# Sensor8A_V2.net
KiCad netlist of a schematic drawn in EAGLE
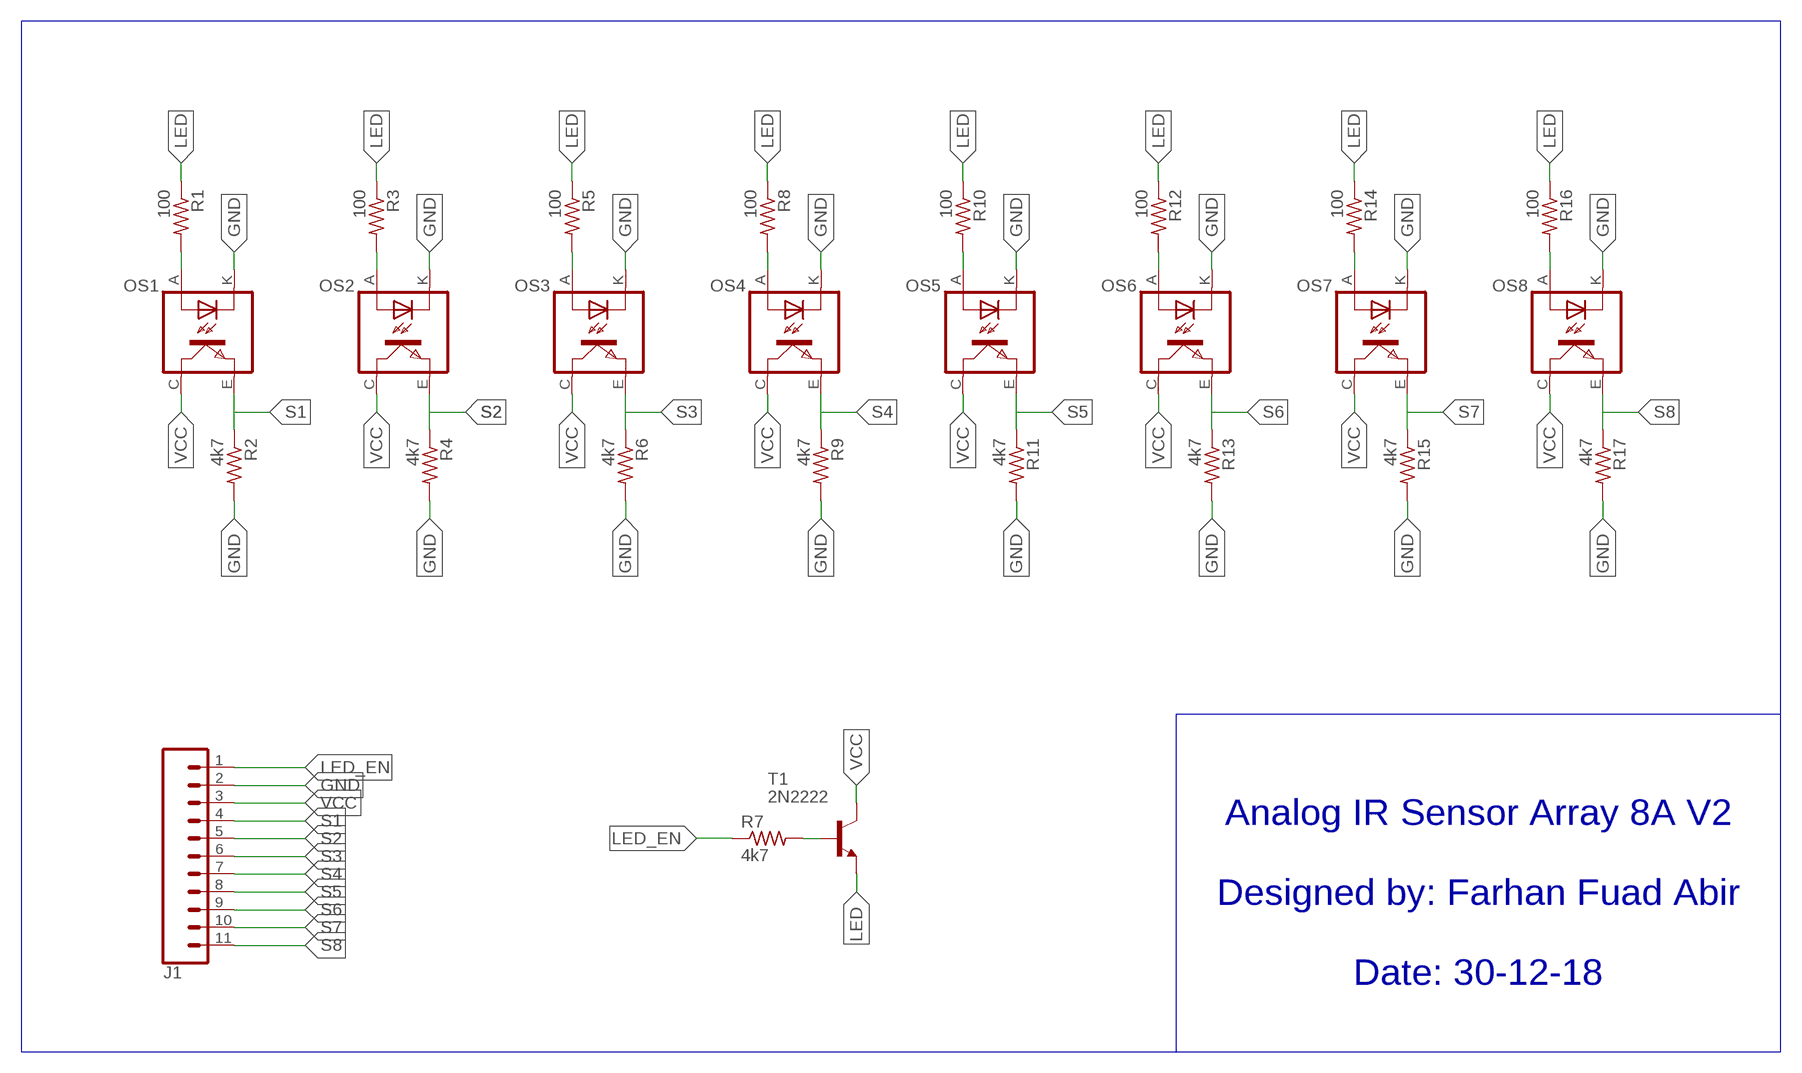
[diagram p0: schematic, sheet 1]

(export (version "E")
  (design (tool "Eeschema 10.0.6"))
  (components
    (comp (ref "J1")
      (value "CONN_11LONGPADS")
      (footprint "eagle-import:1X11_LONGPADS")
      (libsource (lib "eagle-import") (part "CONN_11LONGPADS"))
    )
    (comp (ref "OS1")
      (value "TCRT5000")
      (footprint "eagle-import:TCRT5000")
      (libsource (lib "eagle-import") (part "TCRT5000"))
    )
    (comp (ref "OS2")
      (value "TCRT5000")
      (footprint "eagle-import:TCRT5000")
      (libsource (lib "eagle-import") (part "TCRT5000"))
    )
    (comp (ref "OS3")
      (value "TCRT5000")
      (footprint "eagle-import:TCRT5000")
      (libsource (lib "eagle-import") (part "TCRT5000"))
    )
    (comp (ref "OS4")
      (value "TCRT5000")
      (footprint "eagle-import:TCRT5000")
      (libsource (lib "eagle-import") (part "TCRT5000"))
    )
    (comp (ref "OS5")
      (value "TCRT5000")
      (footprint "eagle-import:TCRT5000")
      (libsource (lib "eagle-import") (part "TCRT5000"))
    )
    (comp (ref "OS6")
      (value "TCRT5000")
      (footprint "eagle-import:TCRT5000")
      (libsource (lib "eagle-import") (part "TCRT5000"))
    )
    (comp (ref "OS7")
      (value "TCRT5000")
      (footprint "eagle-import:TCRT5000")
      (libsource (lib "eagle-import") (part "TCRT5000"))
    )
    (comp (ref "OS8")
      (value "TCRT5000")
      (footprint "eagle-import:TCRT5000")
      (libsource (lib "eagle-import") (part "TCRT5000"))
    )
    (comp (ref "R1")
      (value "100")
      (footprint "eagle-import:0204_7")
      (fields (field (name "SPICEPREFIX") "R"))
      (libsource (lib "eagle-import") (part "R-US_0204/7"))
    )
    (comp (ref "R2")
      (value "4k7")
      (footprint "eagle-import:0204_7")
      (fields (field (name "SPICEPREFIX") "R"))
      (libsource (lib "eagle-import") (part "R-US_0204/7"))
    )
    (comp (ref "R3")
      (value "100")
      (footprint "eagle-import:0204_7")
      (fields (field (name "SPICEPREFIX") "R"))
      (libsource (lib "eagle-import") (part "R-US_0204/7"))
    )
    (comp (ref "R4")
      (value "4k7")
      (footprint "eagle-import:0204_7")
      (fields (field (name "SPICEPREFIX") "R"))
      (libsource (lib "eagle-import") (part "R-US_0204/7"))
    )
    (comp (ref "R5")
      (value "100")
      (footprint "eagle-import:0204_7")
      (fields (field (name "SPICEPREFIX") "R"))
      (libsource (lib "eagle-import") (part "R-US_0204/7"))
    )
    (comp (ref "R6")
      (value "4k7")
      (footprint "eagle-import:0204_7")
      (fields (field (name "SPICEPREFIX") "R"))
      (libsource (lib "eagle-import") (part "R-US_0204/7"))
    )
    (comp (ref "R7")
      (value "4k7")
      (footprint "eagle-import:0204_7")
      (fields (field (name "SPICEPREFIX") "R"))
      (libsource (lib "eagle-import") (part "R-US_0204/7"))
    )
    (comp (ref "R8")
      (value "100")
      (footprint "eagle-import:0204_7")
      (fields (field (name "SPICEPREFIX") "R"))
      (libsource (lib "eagle-import") (part "R-US_0204/7"))
    )
    (comp (ref "R9")
      (value "4k7")
      (footprint "eagle-import:0204_7")
      (fields (field (name "SPICEPREFIX") "R"))
      (libsource (lib "eagle-import") (part "R-US_0204/7"))
    )
    (comp (ref "R10")
      (value "100")
      (footprint "eagle-import:0204_7")
      (fields (field (name "SPICEPREFIX") "R"))
      (libsource (lib "eagle-import") (part "R-US_0204/7"))
    )
    (comp (ref "R11")
      (value "4k7")
      (footprint "eagle-import:0204_7")
      (fields (field (name "SPICEPREFIX") "R"))
      (libsource (lib "eagle-import") (part "R-US_0204/7"))
    )
    (comp (ref "R12")
      (value "100")
      (footprint "eagle-import:0204_7")
      (fields (field (name "SPICEPREFIX") "R"))
      (libsource (lib "eagle-import") (part "R-US_0204/7"))
    )
    (comp (ref "R13")
      (value "4k7")
      (footprint "eagle-import:0204_7")
      (fields (field (name "SPICEPREFIX") "R"))
      (libsource (lib "eagle-import") (part "R-US_0204/7"))
    )
    (comp (ref "R14")
      (value "100")
      (footprint "eagle-import:0204_7")
      (fields (field (name "SPICEPREFIX") "R"))
      (libsource (lib "eagle-import") (part "R-US_0204/7"))
    )
    (comp (ref "R15")
      (value "4k7")
      (footprint "eagle-import:0204_7")
      (fields (field (name "SPICEPREFIX") "R"))
      (libsource (lib "eagle-import") (part "R-US_0204/7"))
    )
    (comp (ref "R16")
      (value "100")
      (footprint "eagle-import:0204_7")
      (fields (field (name "SPICEPREFIX") "R"))
      (libsource (lib "eagle-import") (part "R-US_0204/7"))
    )
    (comp (ref "R17")
      (value "4k7")
      (footprint "eagle-import:0204_7")
      (fields (field (name "SPICEPREFIX") "R"))
      (libsource (lib "eagle-import") (part "R-US_0204/7"))
    )
    (comp (ref "T1")
      (value "2N2222")
      (footprint "eagle-import:TO92-EBC-OVAL")
      (libsource (lib "eagle-import") (part "2N2222"))
    )
  )
  (nets
    (net (code "1") (name "GND") (class "Default")
      (node (ref "J1") (pin "2") (pinfunction "2_2") (pintype "passive"))
      (node (ref "OS1") (pin "K") (pinfunction "CATHODE_K") (pintype "passive"))
      (node (ref "OS2") (pin "K") (pinfunction "CATHODE_K") (pintype "passive"))
      (node (ref "OS3") (pin "K") (pinfunction "CATHODE_K") (pintype "passive"))
      (node (ref "OS4") (pin "K") (pinfunction "CATHODE_K") (pintype "passive"))
      (node (ref "OS5") (pin "K") (pinfunction "CATHODE_K") (pintype "passive"))
      (node (ref "OS6") (pin "K") (pinfunction "CATHODE_K") (pintype "passive"))
      (node (ref "OS7") (pin "K") (pinfunction "CATHODE_K") (pintype "passive"))
      (node (ref "OS8") (pin "K") (pinfunction "CATHODE_K") (pintype "passive"))
      (node (ref "R11") (pin "2") (pinfunction "2_2") (pintype "passive"))
      (node (ref "R13") (pin "2") (pinfunction "2_2") (pintype "passive"))
      (node (ref "R15") (pin "2") (pinfunction "2_2") (pintype "passive"))
      (node (ref "R17") (pin "2") (pinfunction "2_2") (pintype "passive"))
      (node (ref "R2") (pin "2") (pinfunction "2_2") (pintype "passive"))
      (node (ref "R4") (pin "2") (pinfunction "2_2") (pintype "passive"))
      (node (ref "R6") (pin "2") (pinfunction "2_2") (pintype "passive"))
      (node (ref "R9") (pin "2") (pinfunction "2_2") (pintype "passive"))
    )
    (net (code "2") (name "LED") (class "Default")
      (node (ref "R1") (pin "1") (pinfunction "1_1") (pintype "passive"))
      (node (ref "R10") (pin "1") (pinfunction "1_1") (pintype "passive"))
      (node (ref "R12") (pin "1") (pinfunction "1_1") (pintype "passive"))
      (node (ref "R14") (pin "1") (pinfunction "1_1") (pintype "passive"))
      (node (ref "R16") (pin "1") (pinfunction "1_1") (pintype "passive"))
      (node (ref "R3") (pin "1") (pinfunction "1_1") (pintype "passive"))
      (node (ref "R5") (pin "1") (pinfunction "1_1") (pintype "passive"))
      (node (ref "R8") (pin "1") (pinfunction "1_1") (pintype "passive"))
      (node (ref "T1") (pin "E") (pinfunction "E_E") (pintype "passive"))
    )
    (net (code "3") (name "LED_EN") (class "Default")
      (node (ref "J1") (pin "1") (pinfunction "1_1") (pintype "passive"))
      (node (ref "R7") (pin "1") (pinfunction "1_1") (pintype "passive"))
    )
    (net (code "4") (name "Net-(OS1-ANODE)") (class "Default")
      (node (ref "OS1") (pin "A") (pinfunction "ANODE_A") (pintype "passive"))
      (node (ref "R1") (pin "2") (pinfunction "2_2") (pintype "passive"))
    )
    (net (code "5") (name "Net-(OS2-ANODE)") (class "Default")
      (node (ref "OS2") (pin "A") (pinfunction "ANODE_A") (pintype "passive"))
      (node (ref "R3") (pin "2") (pinfunction "2_2") (pintype "passive"))
    )
    (net (code "6") (name "Net-(OS3-ANODE)") (class "Default")
      (node (ref "OS3") (pin "A") (pinfunction "ANODE_A") (pintype "passive"))
      (node (ref "R5") (pin "2") (pinfunction "2_2") (pintype "passive"))
    )
    (net (code "7") (name "Net-(OS4-ANODE)") (class "Default")
      (node (ref "OS4") (pin "A") (pinfunction "ANODE_A") (pintype "passive"))
      (node (ref "R8") (pin "2") (pinfunction "2_2") (pintype "passive"))
    )
    (net (code "8") (name "Net-(OS5-ANODE)") (class "Default")
      (node (ref "OS5") (pin "A") (pinfunction "ANODE_A") (pintype "passive"))
      (node (ref "R10") (pin "2") (pinfunction "2_2") (pintype "passive"))
    )
    (net (code "9") (name "Net-(OS6-ANODE)") (class "Default")
      (node (ref "OS6") (pin "A") (pinfunction "ANODE_A") (pintype "passive"))
      (node (ref "R12") (pin "2") (pinfunction "2_2") (pintype "passive"))
    )
    (net (code "10") (name "Net-(OS7-ANODE)") (class "Default")
      (node (ref "OS7") (pin "A") (pinfunction "ANODE_A") (pintype "passive"))
      (node (ref "R14") (pin "2") (pinfunction "2_2") (pintype "passive"))
    )
    (net (code "11") (name "Net-(OS8-ANODE)") (class "Default")
      (node (ref "OS8") (pin "A") (pinfunction "ANODE_A") (pintype "passive"))
      (node (ref "R16") (pin "2") (pinfunction "2_2") (pintype "passive"))
    )
    (net (code "12") (name "Net-(R7-Pad2)") (class "Default")
      (node (ref "R7") (pin "2") (pinfunction "2_2") (pintype "passive"))
      (node (ref "T1") (pin "B") (pinfunction "B_B") (pintype "passive"))
    )
    (net (code "13") (name "S1") (class "Default")
      (node (ref "J1") (pin "4") (pinfunction "4_4") (pintype "passive"))
      (node (ref "OS1") (pin "E") (pinfunction "EMITTER_E") (pintype "passive"))
      (node (ref "R2") (pin "1") (pinfunction "1_1") (pintype "passive"))
    )
    (net (code "14") (name "S2") (class "Default")
      (node (ref "J1") (pin "5") (pinfunction "5_5") (pintype "passive"))
      (node (ref "OS2") (pin "E") (pinfunction "EMITTER_E") (pintype "passive"))
      (node (ref "R4") (pin "1") (pinfunction "1_1") (pintype "passive"))
    )
    (net (code "15") (name "S3") (class "Default")
      (node (ref "J1") (pin "6") (pinfunction "6_6") (pintype "passive"))
      (node (ref "OS3") (pin "E") (pinfunction "EMITTER_E") (pintype "passive"))
      (node (ref "R6") (pin "1") (pinfunction "1_1") (pintype "passive"))
    )
    (net (code "16") (name "S4") (class "Default")
      (node (ref "J1") (pin "7") (pinfunction "7_7") (pintype "passive"))
      (node (ref "OS4") (pin "E") (pinfunction "EMITTER_E") (pintype "passive"))
      (node (ref "R9") (pin "1") (pinfunction "1_1") (pintype "passive"))
    )
    (net (code "17") (name "S5") (class "Default")
      (node (ref "J1") (pin "8") (pinfunction "8_8") (pintype "passive"))
      (node (ref "OS5") (pin "E") (pinfunction "EMITTER_E") (pintype "passive"))
      (node (ref "R11") (pin "1") (pinfunction "1_1") (pintype "passive"))
    )
    (net (code "18") (name "S6") (class "Default")
      (node (ref "J1") (pin "9") (pinfunction "9_9") (pintype "passive"))
      (node (ref "OS6") (pin "E") (pinfunction "EMITTER_E") (pintype "passive"))
      (node (ref "R13") (pin "1") (pinfunction "1_1") (pintype "passive"))
    )
    (net (code "19") (name "S7") (class "Default")
      (node (ref "J1") (pin "10") (pinfunction "10_10") (pintype "passive"))
      (node (ref "OS7") (pin "E") (pinfunction "EMITTER_E") (pintype "passive"))
      (node (ref "R15") (pin "1") (pinfunction "1_1") (pintype "passive"))
    )
    (net (code "20") (name "S8") (class "Default")
      (node (ref "J1") (pin "11") (pinfunction "11_11") (pintype "passive"))
      (node (ref "OS8") (pin "E") (pinfunction "EMITTER_E") (pintype "passive"))
      (node (ref "R17") (pin "1") (pinfunction "1_1") (pintype "passive"))
    )
    (net (code "21") (name "VCC") (class "Default")
      (node (ref "J1") (pin "3") (pinfunction "3_3") (pintype "passive"))
      (node (ref "OS1") (pin "C") (pinfunction "COLLECTOR_C") (pintype "passive"))
      (node (ref "OS2") (pin "C") (pinfunction "COLLECTOR_C") (pintype "passive"))
      (node (ref "OS3") (pin "C") (pinfunction "COLLECTOR_C") (pintype "passive"))
      (node (ref "OS4") (pin "C") (pinfunction "COLLECTOR_C") (pintype "passive"))
      (node (ref "OS5") (pin "C") (pinfunction "COLLECTOR_C") (pintype "passive"))
      (node (ref "OS6") (pin "C") (pinfunction "COLLECTOR_C") (pintype "passive"))
      (node (ref "OS7") (pin "C") (pinfunction "COLLECTOR_C") (pintype "passive"))
      (node (ref "OS8") (pin "C") (pinfunction "COLLECTOR_C") (pintype "passive"))
      (node (ref "T1") (pin "C") (pinfunction "C_C") (pintype "passive"))
    )
  )
)
